# Wireless.net
KiCad netlist of a schematic drawn in Altium Designer
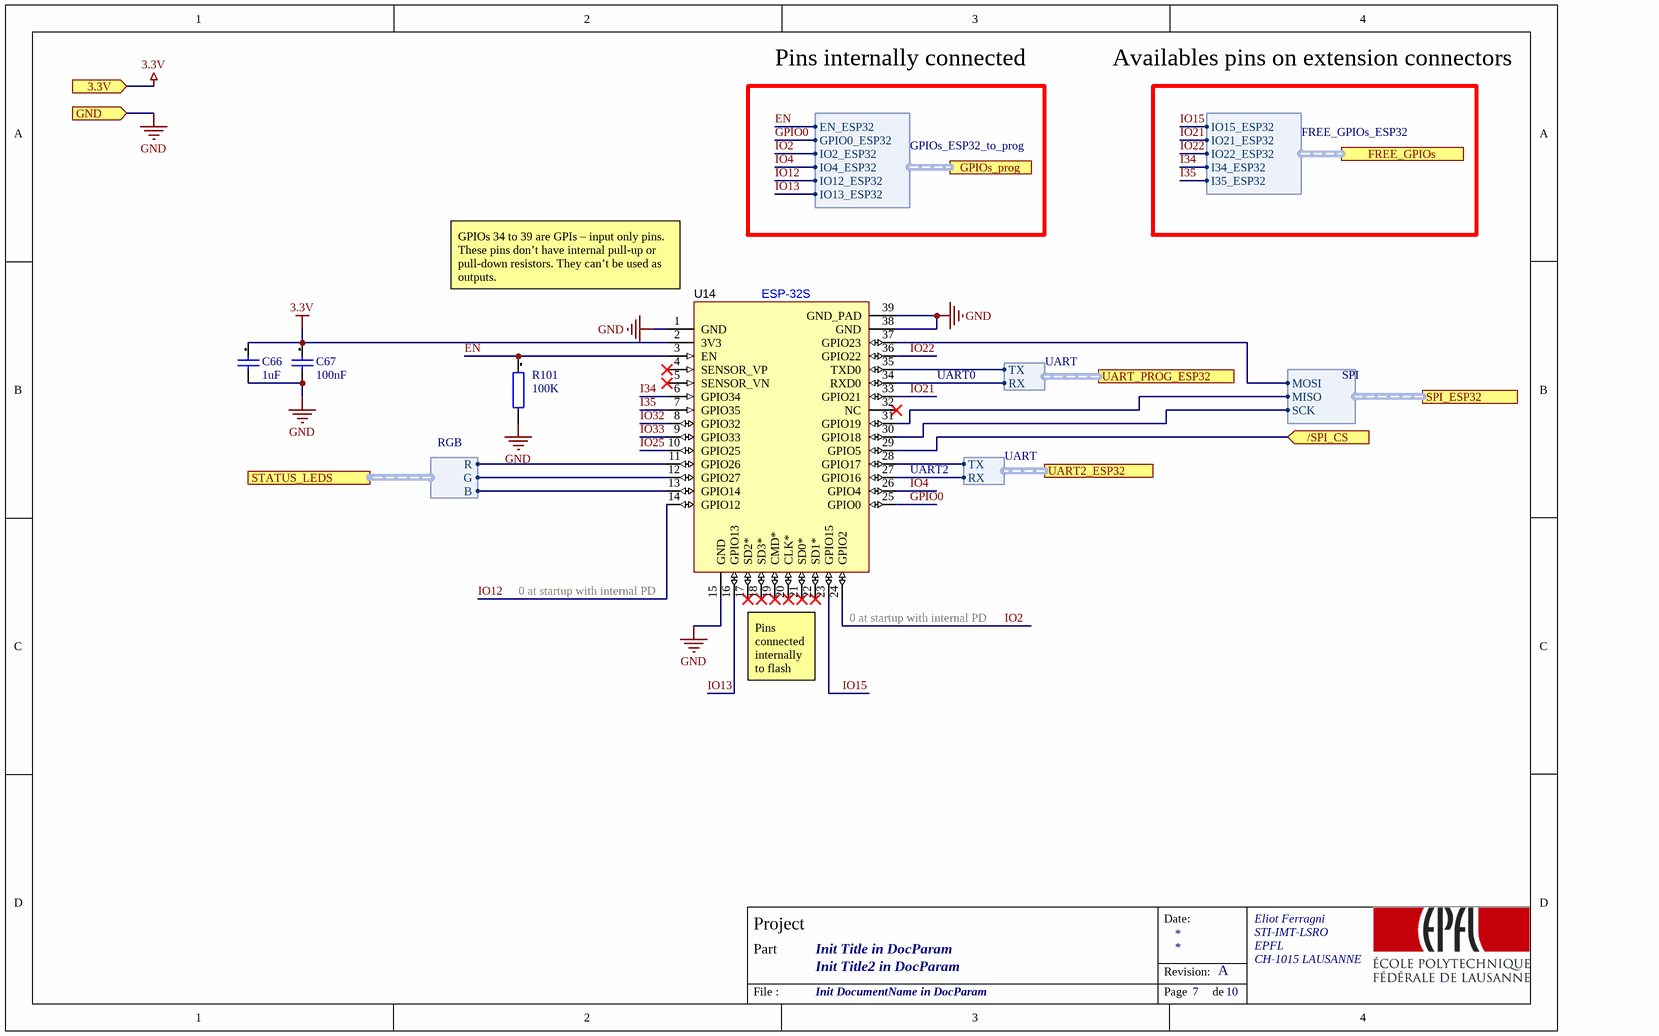
[diagram p0: Wireless.SchDoc]

(export (version "E")
  (design (tool "Eeschema 10.0.6"))
  (components
    (comp (ref "C66")
      (value "1uF")
      (footprint "CAPC0201(0603)33_L")
      (description "Capacitor TBD 0201")
      (libsource (lib "LSRO1Altium") (part "CAP-NP"))
    )
    (comp (ref "C67")
      (value "100nF")
      (footprint "CAPC0201(0603)33_L")
      (description "Capacitor TBD 0201")
      (libsource (lib "LSRO1Altium") (part "CAP-NP"))
    )
    (comp (ref "R101")
      (value "100K")
      (footprint "RESC0201(0603)_L")
      (description "Resistor ToDo 0201")
      (libsource (lib "LSRO1Altium") (part "RES"))
    )
    (comp (ref "U14")
      (value "ESP-32S")
      (footprint "ESP-32S")
      (description "Wi-Fi BT BLE MCU Module")
      (fields (field (name "MANUFACTURER") "TEXAS INSTRUMENTS"))
      (libsource (lib "Schlib") (part "ESP-32S"))
    )
  )
  (nets
    (net (code "6") (name "/B") (class "Default")
      (node (ref "U14") (pin "13") (pinfunction "GPIO14_13") (pintype "bidirectional"))
    )
    (net (code "7") (name "/EN") (class "Default")
      (node (ref "R101") (pin "1") (pinfunction "1_1") (pintype "passive"))
      (node (ref "U14") (pin "3") (pinfunction "EN_3") (pintype "input"))
    )
    (net (code "8") (name "/G") (class "Default")
      (node (ref "U14") (pin "12") (pinfunction "GPIO27_12") (pintype "bidirectional"))
    )
    (net (code "9") (name "/GPIO0") (class "Default")
      (node (ref "U14") (pin "25") (pinfunction "GPIO0_25") (pintype "bidirectional"))
    )
    (net (code "10") (name "/I34") (class "Default")
      (node (ref "U14") (pin "6") (pinfunction "GPIO34_6") (pintype "input"))
    )
    (net (code "11") (name "/I35") (class "Default")
      (node (ref "U14") (pin "7") (pinfunction "GPIO35_7") (pintype "input"))
    )
    (net (code "12") (name "/IO2") (class "Default")
      (node (ref "U14") (pin "24") (pinfunction "GPIO2_24") (pintype "bidirectional"))
    )
    (net (code "13") (name "/IO4") (class "Default")
      (node (ref "U14") (pin "26") (pinfunction "GPIO4_26") (pintype "bidirectional"))
    )
    (net (code "14") (name "/IO12") (class "Default")
      (node (ref "U14") (pin "14") (pinfunction "GPIO12_14") (pintype "bidirectional"))
    )
    (net (code "15") (name "/IO13") (class "Default")
      (node (ref "U14") (pin "16") (pinfunction "GPIO13_16") (pintype "bidirectional"))
    )
    (net (code "16") (name "/IO15") (class "Default")
      (node (ref "U14") (pin "23") (pinfunction "GPIO15_23") (pintype "bidirectional"))
    )
    (net (code "17") (name "/IO21") (class "Default")
      (node (ref "U14") (pin "33") (pinfunction "GPIO21_33") (pintype "bidirectional"))
    )
    (net (code "18") (name "/IO22") (class "Default")
      (node (ref "U14") (pin "36") (pinfunction "GPIO22_36") (pintype "bidirectional"))
    )
    (net (code "19") (name "/IO25") (class "Default")
      (node (ref "U14") (pin "10") (pinfunction "GPIO25_10") (pintype "bidirectional"))
    )
    (net (code "20") (name "/IO32") (class "Default")
      (node (ref "U14") (pin "8") (pinfunction "GPIO32_8") (pintype "bidirectional"))
    )
    (net (code "21") (name "/IO33") (class "Default")
      (node (ref "U14") (pin "9") (pinfunction "GPIO33_9") (pintype "bidirectional"))
    )
    (net (code "22") (name "/MISO") (class "Default")
      (node (ref "U14") (pin "31") (pinfunction "GPIO19_31") (pintype "bidirectional"))
    )
    (net (code "23") (name "/MOSI") (class "Default")
      (node (ref "U14") (pin "37") (pinfunction "GPIO23_37") (pintype "bidirectional"))
    )
    (net (code "24") (name "/R") (class "Default")
      (node (ref "U14") (pin "11") (pinfunction "GPIO26_11") (pintype "bidirectional"))
    )
    (net (code "25") (name "/SCK") (class "Default")
      (node (ref "U14") (pin "30") (pinfunction "GPIO18_30") (pintype "bidirectional"))
    )
    (net (code "31") (name "/{slash}SPI_CS") (class "Default")
      (node (ref "U14") (pin "29") (pinfunction "GPIO5_29") (pintype "bidirectional"))
    )
    (net (code "32") (name "3.3V") (class "Default")
      (node (ref "C66") (pin "1") (pinfunction "1_1") (pintype "passive"))
      (node (ref "C67") (pin "1") (pinfunction "1_1") (pintype "passive"))
      (node (ref "U14") (pin "2") (pinfunction "3V3_2") (pintype "power_in"))
    )
    (net (code "33") (name "GND") (class "Default")
      (node (ref "C66") (pin "2") (pinfunction "2_2") (pintype "passive"))
      (node (ref "C67") (pin "2") (pinfunction "2_2") (pintype "passive"))
      (node (ref "R101") (pin "2") (pinfunction "2_2") (pintype "passive"))
      (node (ref "U14") (pin "1") (pinfunction "GND_1") (pintype "power_in"))
      (node (ref "U14") (pin "15") (pinfunction "GND_15") (pintype "power_in"))
      (node (ref "U14") (pin "38") (pinfunction "GND_38") (pintype "power_in"))
      (node (ref "U14") (pin "39") (pinfunction "GND_PAD_39") (pintype "power_in"))
    )
    (net (code "34") (name "unconnected-(U14-CLK*-Pad20)") (class "Default")
      (node (ref "U14") (pin "20") (pinfunction "CLK*_20") (pintype "bidirectional+no_connect"))
    )
    (net (code "35") (name "unconnected-(U14-CMD*-Pad19)") (class "Default")
      (node (ref "U14") (pin "19") (pinfunction "CMD*_19") (pintype "bidirectional+no_connect"))
    )
    (net (code "36") (name "unconnected-(U14-GPIO16-Pad27)") (class "Default")
      (node (ref "U14") (pin "27") (pinfunction "GPIO16_27") (pintype "bidirectional"))
    )
    (net (code "37") (name "unconnected-(U14-GPIO17-Pad28)") (class "Default")
      (node (ref "U14") (pin "28") (pinfunction "GPIO17_28") (pintype "bidirectional"))
    )
    (net (code "38") (name "unconnected-(U14-NC-Pad32)") (class "Default")
      (node (ref "U14") (pin "32") (pinfunction "NC_32") (pintype "passive+no_connect"))
    )
    (net (code "39") (name "unconnected-(U14-RXD0-Pad34)") (class "Default")
      (node (ref "U14") (pin "34") (pinfunction "RXD0_34") (pintype "bidirectional"))
    )
    (net (code "40") (name "unconnected-(U14-SD0*-Pad21)") (class "Default")
      (node (ref "U14") (pin "21") (pinfunction "SD0*_21") (pintype "bidirectional+no_connect"))
    )
    (net (code "41") (name "unconnected-(U14-SD1*-Pad22)") (class "Default")
      (node (ref "U14") (pin "22") (pinfunction "SD1*_22") (pintype "bidirectional+no_connect"))
    )
    (net (code "42") (name "unconnected-(U14-SD2*-Pad17)") (class "Default")
      (node (ref "U14") (pin "17") (pinfunction "SD2*_17") (pintype "bidirectional+no_connect"))
    )
    (net (code "43") (name "unconnected-(U14-SD3*-Pad18)") (class "Default")
      (node (ref "U14") (pin "18") (pinfunction "SD3*_18") (pintype "bidirectional+no_connect"))
    )
    (net (code "44") (name "unconnected-(U14-SENSOR_VN-Pad5)") (class "Default")
      (node (ref "U14") (pin "5") (pinfunction "SENSOR_VN_5") (pintype "input+no_connect"))
    )
    (net (code "45") (name "unconnected-(U14-SENSOR_VP-Pad4)") (class "Default")
      (node (ref "U14") (pin "4") (pinfunction "SENSOR_VP_4") (pintype "input+no_connect"))
    )
    (net (code "46") (name "unconnected-(U14-TXD0-Pad35)") (class "Default")
      (node (ref "U14") (pin "35") (pinfunction "TXD0_35") (pintype "bidirectional"))
    )
  )
)
